# Voicecard-SMRMU-v02.net
KiCad netlist of a schematic drawn in EAGLE
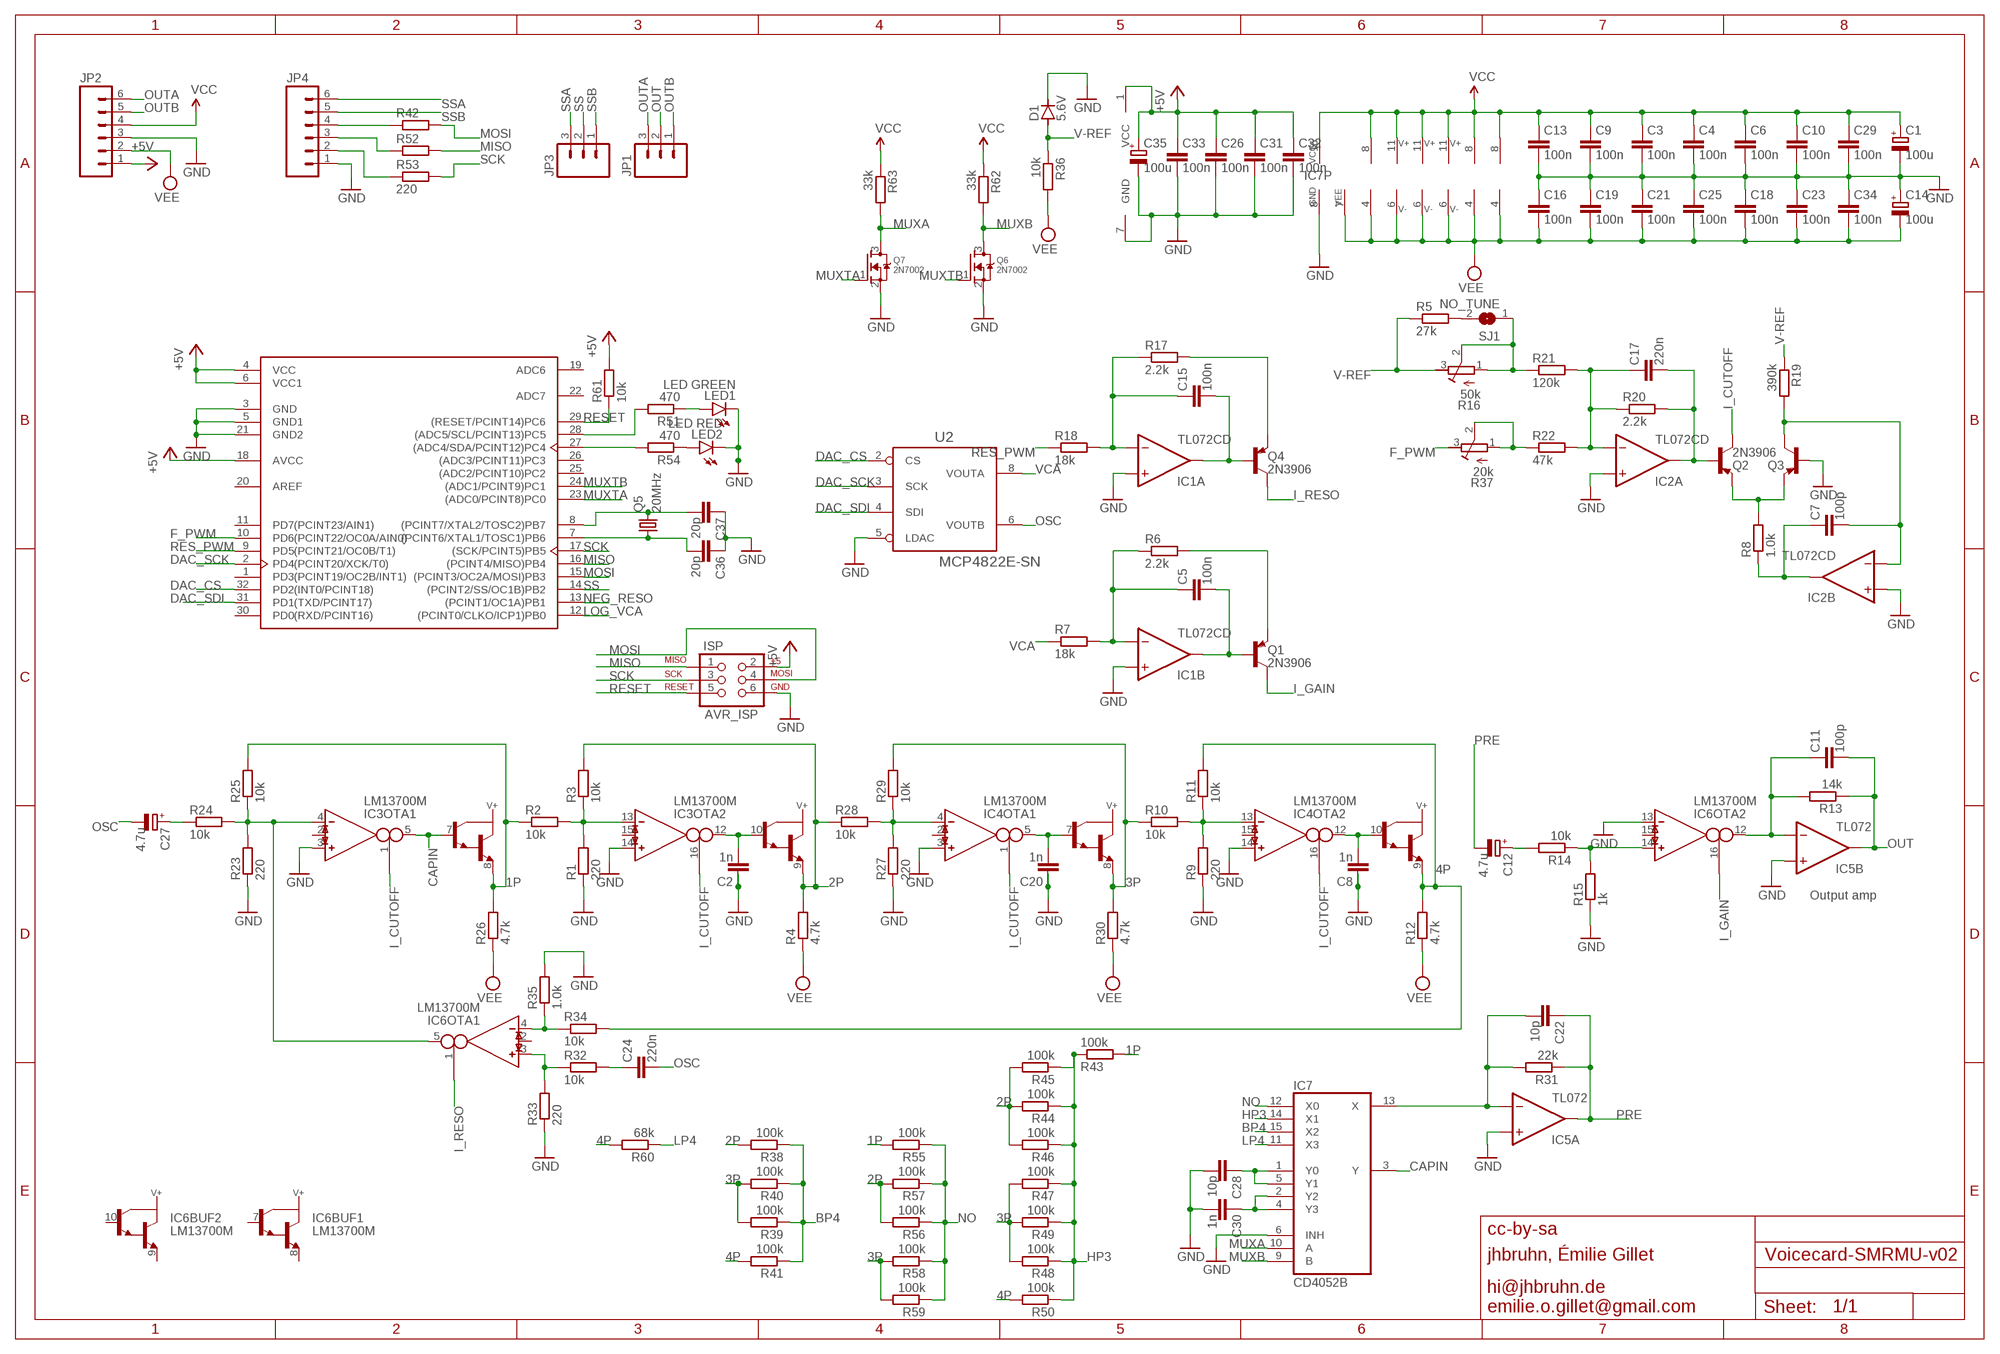
[diagram p0: schematic, sheet 1]

(export (version "E")
  (design (tool "Eeschema 10.0.6"))
  (components
    (comp (ref "C1")
      (value "100u")
      (footprint "eagle-import:UD-6,3X7,7_NICHICON")
      (libsource (lib "eagle-import") (part "CPOL-EUUD-6,3X7,7"))
    )
    (comp (ref "C2")
      (value "1n")
      (footprint "eagle-import:C0603")
      (libsource (lib "eagle-import") (part "C-EUC0603"))
    )
    (comp (ref "C3")
      (value "100n")
      (footprint "eagle-import:C0603")
      (libsource (lib "eagle-import") (part "C-EUC0603"))
    )
    (comp (ref "C4")
      (value "100n")
      (footprint "eagle-import:C0603")
      (libsource (lib "eagle-import") (part "C-EUC0603"))
    )
    (comp (ref "C5")
      (value "100n")
      (footprint "eagle-import:C0603")
      (libsource (lib "eagle-import") (part "C-EUC0603"))
    )
    (comp (ref "C6")
      (value "100n")
      (footprint "eagle-import:C0603")
      (libsource (lib "eagle-import") (part "C-EUC0603"))
    )
    (comp (ref "C7")
      (value "100p")
      (footprint "eagle-import:C0603")
      (libsource (lib "eagle-import") (part "C-EUC0603"))
    )
    (comp (ref "C8")
      (value "1n")
      (footprint "eagle-import:C0603")
      (libsource (lib "eagle-import") (part "C-EUC0603"))
    )
    (comp (ref "C9")
      (value "100n")
      (footprint "eagle-import:C0603")
      (libsource (lib "eagle-import") (part "C-EUC0603"))
    )
    (comp (ref "C10")
      (value "100n")
      (footprint "eagle-import:C0603")
      (libsource (lib "eagle-import") (part "C-EUC0603"))
    )
    (comp (ref "C11")
      (value "100p")
      (footprint "eagle-import:C0603")
      (libsource (lib "eagle-import") (part "C-EUC0603"))
    )
    (comp (ref "C12")
      (value "4.7u")
      (footprint "eagle-import:UD-5X5,8_NICHICON")
      (libsource (lib "eagle-import") (part "CPOL-EUUD-5X5,8"))
    )
    (comp (ref "C13")
      (value "100n")
      (footprint "eagle-import:C0603")
      (libsource (lib "eagle-import") (part "C-EUC0603"))
    )
    (comp (ref "C14")
      (value "100u")
      (footprint "eagle-import:UD-6,3X7,7_NICHICON")
      (libsource (lib "eagle-import") (part "CPOL-EUUD-6,3X7,7"))
    )
    (comp (ref "C15")
      (value "100n")
      (footprint "eagle-import:C0603")
      (libsource (lib "eagle-import") (part "C-EUC0603"))
    )
    (comp (ref "C16")
      (value "100n")
      (footprint "eagle-import:C0603")
      (libsource (lib "eagle-import") (part "C-EUC0603"))
    )
    (comp (ref "C17")
      (value "220n")
      (footprint "eagle-import:C0603")
      (libsource (lib "eagle-import") (part "C-EUC0603"))
    )
    (comp (ref "C18")
      (value "100n")
      (footprint "eagle-import:C0603")
      (libsource (lib "eagle-import") (part "C-EUC0603"))
    )
    (comp (ref "C19")
      (value "100n")
      (footprint "eagle-import:C0603")
      (libsource (lib "eagle-import") (part "C-EUC0603"))
    )
    (comp (ref "C20")
      (value "1n")
      (footprint "eagle-import:C0603")
      (libsource (lib "eagle-import") (part "C-EUC0603"))
    )
    (comp (ref "C21")
      (value "100n")
      (footprint "eagle-import:C0603")
      (libsource (lib "eagle-import") (part "C-EUC0603"))
    )
    (comp (ref "C22")
      (value "10p")
      (footprint "eagle-import:C0603")
      (libsource (lib "eagle-import") (part "C-EUC0603"))
    )
    (comp (ref "C23")
      (value "100n")
      (footprint "eagle-import:C0603")
      (libsource (lib "eagle-import") (part "C-EUC0603"))
    )
    (comp (ref "C24")
      (value "220n")
      (footprint "eagle-import:C0603")
      (libsource (lib "eagle-import") (part "C-EUC0603"))
    )
    (comp (ref "C25")
      (value "100n")
      (footprint "eagle-import:C0603")
      (libsource (lib "eagle-import") (part "C-EUC0603"))
    )
    (comp (ref "C26")
      (value "100n")
      (footprint "eagle-import:C0603")
      (libsource (lib "eagle-import") (part "C-EUC0603"))
    )
    (comp (ref "C27")
      (value "4.7u")
      (footprint "eagle-import:UD-5X5,8_NICHICON")
      (libsource (lib "eagle-import") (part "CPOL-EUUD-5X5,8"))
    )
    (comp (ref "C28")
      (value "10p")
      (footprint "eagle-import:C0603")
      (libsource (lib "eagle-import") (part "C-EUC0603"))
    )
    (comp (ref "C29")
      (value "100n")
      (footprint "eagle-import:C0603")
      (libsource (lib "eagle-import") (part "C-EUC0603"))
    )
    (comp (ref "C30")
      (value "1n")
      (footprint "eagle-import:C0603")
      (libsource (lib "eagle-import") (part "C-EUC0603"))
    )
    (comp (ref "C31")
      (value "100n")
      (footprint "eagle-import:C0603")
      (libsource (lib "eagle-import") (part "C-EUC0603"))
    )
    (comp (ref "C32")
      (value "100n")
      (footprint "eagle-import:C0603")
      (libsource (lib "eagle-import") (part "C-EUC0603"))
    )
    (comp (ref "C33")
      (value "100n")
      (footprint "eagle-import:C0603")
      (libsource (lib "eagle-import") (part "C-EUC0603"))
    )
    (comp (ref "C34")
      (value "100n")
      (footprint "eagle-import:C0603")
      (libsource (lib "eagle-import") (part "C-EUC0603"))
    )
    (comp (ref "C35")
      (value "100u")
      (footprint "eagle-import:UD-6,3X7,7_NICHICON")
      (libsource (lib "eagle-import") (part "CPOL-EUUD-6,3X7,7"))
    )
    (comp (ref "C36")
      (value "20p")
      (footprint "eagle-import:C0603")
      (libsource (lib "eagle-import") (part "C-EUC0603"))
    )
    (comp (ref "C37")
      (value "20p")
      (footprint "eagle-import:C0603")
      (libsource (lib "eagle-import") (part "C-EUC0603"))
    )
    (comp (ref "D1")
      (value "5.6V")
      (footprint "eagle-import:MELF-MLL34")
      (libsource (lib "eagle-import") (part "DIODE-LL-34"))
    )
    (comp (ref "IC1")
      (value "TL072CD")
      (footprint "eagle-import:SOIC8")
      (libsource (lib "eagle-import") (part "TL072DC"))
    )
    (comp (ref "IC2")
      (value "TL072CD")
      (footprint "eagle-import:SOIC8")
      (libsource (lib "eagle-import") (part "TL072DC"))
    )
    (comp (ref "IC3")
      (value "LM13700M")
      (footprint "eagle-import:SO16")
      (libsource (lib "eagle-import") (part "LM13700M"))
    )
    (comp (ref "IC4")
      (value "LM13700M")
      (footprint "eagle-import:SO16")
      (libsource (lib "eagle-import") (part "LM13700M"))
    )
    (comp (ref "IC5")
      (value "TL072")
      (footprint "eagle-import:SOIC8")
      (libsource (lib "eagle-import") (part "TL072DC"))
    )
    (comp (ref "IC6")
      (value "LM13700M")
      (footprint "eagle-import:SO16")
      (libsource (lib "eagle-import") (part "LM13700M"))
    )
    (comp (ref "IC7")
      (value "CD4052B")
      (footprint "eagle-import:SOIC16N")
      (libsource (lib "eagle-import") (part "CD4052B"))
    )
    (comp (ref "ISP")
      (value "AVR_ISP")
      (footprint "eagle-import:2X3")
      (libsource (lib "eagle-import") (part "AVR_SPI_PRG_6PTH"))
    )
    (comp (ref "JP1")
      (value "M03PTH")
      (footprint "eagle-import:1X03")
      (libsource (lib "eagle-import") (part "M03PTH"))
    )
    (comp (ref "JP2")
      (value "M06SIP")
      (footprint "eagle-import:1X06")
      (libsource (lib "eagle-import") (part "M06SIP"))
    )
    (comp (ref "JP3")
      (value "M03PTH")
      (footprint "eagle-import:1X03")
      (libsource (lib "eagle-import") (part "M03PTH"))
    )
    (comp (ref "JP4")
      (value "M06SIP")
      (footprint "eagle-import:1X06")
      (libsource (lib "eagle-import") (part "M06SIP"))
    )
    (comp (ref "LED1")
      (value "LED GREEN")
      (footprint "eagle-import:CHIP-LED0603")
      (libsource (lib "eagle-import") (part "LED"))
    )
    (comp (ref "LED2")
      (value "LED RED")
      (footprint "eagle-import:CHIP-LED0603")
      (libsource (lib "eagle-import") (part "LED"))
    )
    (comp (ref "Q1")
      (value "2N3906")
      (footprint "eagle-import:SOT23-BEC")
      (libsource (lib "eagle-import") (part "2N3906"))
    )
    (comp (ref "Q2")
      (value "2N3906")
      (footprint "eagle-import:SOT23-BEC")
      (libsource (lib "eagle-import") (part "2N3906"))
    )
    (comp (ref "Q3")
      (value "2N3906")
      (footprint "eagle-import:SOT23-BEC")
      (libsource (lib "eagle-import") (part "2N3906"))
    )
    (comp (ref "Q4")
      (value "2N3906")
      (footprint "eagle-import:SOT23-BEC")
      (libsource (lib "eagle-import") (part "2N3906"))
    )
    (comp (ref "Q5")
      (value "20MHz")
      (footprint "eagle-import:HC49UP")
      (libsource (lib "eagle-import") (part "CRYSTALHC49UP"))
    )
    (comp (ref "Q6")
      (value "2N7002")
      (footprint "eagle-import:SOT23")
      (libsource (lib "eagle-import") (part "MOSFET-NREFLOW"))
    )
    (comp (ref "Q7")
      (value "2N7002")
      (footprint "eagle-import:SOT23")
      (libsource (lib "eagle-import") (part "MOSFET-NREFLOW"))
    )
    (comp (ref "R1")
      (value "220")
      (footprint "eagle-import:R0603")
      (libsource (lib "eagle-import") (part "R-EU_R0603"))
    )
    (comp (ref "R2")
      (value "10k")
      (footprint "eagle-import:R0603")
      (libsource (lib "eagle-import") (part "R-EU_R0603"))
    )
    (comp (ref "R3")
      (value "10k")
      (footprint "eagle-import:R0603")
      (libsource (lib "eagle-import") (part "R-EU_R0603"))
    )
    (comp (ref "R4")
      (value "4.7k")
      (footprint "eagle-import:R0603")
      (libsource (lib "eagle-import") (part "R-EU_R0603"))
    )
    (comp (ref "R5")
      (value "27k")
      (footprint "eagle-import:R0603")
      (libsource (lib "eagle-import") (part "R-EU_R0603"))
    )
    (comp (ref "R6")
      (value "2.2k")
      (footprint "eagle-import:R0603")
      (libsource (lib "eagle-import") (part "R-EU_R0603"))
    )
    (comp (ref "R7")
      (value "18k")
      (footprint "eagle-import:R0603")
      (libsource (lib "eagle-import") (part "R-EU_R0603"))
    )
    (comp (ref "R8")
      (value "1.0k")
      (footprint "eagle-import:R0603")
      (libsource (lib "eagle-import") (part "R-EU_R0603"))
    )
    (comp (ref "R9")
      (value "220")
      (footprint "eagle-import:R0603")
      (libsource (lib "eagle-import") (part "R-EU_R0603"))
    )
    (comp (ref "R10")
      (value "10k")
      (footprint "eagle-import:R0603")
      (libsource (lib "eagle-import") (part "R-EU_R0603"))
    )
    (comp (ref "R11")
      (value "10k")
      (footprint "eagle-import:R0603")
      (libsource (lib "eagle-import") (part "R-EU_R0603"))
    )
    (comp (ref "R12")
      (value "4.7k")
      (footprint "eagle-import:R0603")
      (libsource (lib "eagle-import") (part "R-EU_R0603"))
    )
    (comp (ref "R13")
      (value "14k")
      (footprint "eagle-import:R0603")
      (libsource (lib "eagle-import") (part "R-EU_R0603"))
    )
    (comp (ref "R14")
      (value "10k")
      (footprint "eagle-import:R0603")
      (libsource (lib "eagle-import") (part "R-EU_R0603"))
    )
    (comp (ref "R15")
      (value "1k")
      (footprint "eagle-import:R0603")
      (libsource (lib "eagle-import") (part "R-EU_R0603"))
    )
    (comp (ref "R16")
      (value "50k")
      (footprint "eagle-import:RTRIM3296P")
      (libsource (lib "eagle-import") (part "R-TRIMM3296P"))
    )
    (comp (ref "R17")
      (value "2.2k")
      (footprint "eagle-import:R0603")
      (libsource (lib "eagle-import") (part "R-EU_R0603"))
    )
    (comp (ref "R18")
      (value "18k")
      (footprint "eagle-import:R0603")
      (libsource (lib "eagle-import") (part "R-EU_R0603"))
    )
    (comp (ref "R19")
      (value "390k")
      (footprint "eagle-import:R0603")
      (libsource (lib "eagle-import") (part "R-EU_R0603"))
    )
    (comp (ref "R20")
      (value "2.2k")
      (footprint "eagle-import:R0603")
      (libsource (lib "eagle-import") (part "R-EU_R0603"))
    )
    (comp (ref "R21")
      (value "120k")
      (footprint "eagle-import:R0603")
      (libsource (lib "eagle-import") (part "R-EU_R0603"))
    )
    (comp (ref "R22")
      (value "47k")
      (footprint "eagle-import:R0603")
      (libsource (lib "eagle-import") (part "R-EU_R0603"))
    )
    (comp (ref "R23")
      (value "220")
      (footprint "eagle-import:R0603")
      (libsource (lib "eagle-import") (part "R-EU_R0603"))
    )
    (comp (ref "R24")
      (value "10k")
      (footprint "eagle-import:R0603")
      (libsource (lib "eagle-import") (part "R-EU_R0603"))
    )
    (comp (ref "R25")
      (value "10k")
      (footprint "eagle-import:R0603")
      (libsource (lib "eagle-import") (part "R-EU_R0603"))
    )
    (comp (ref "R26")
      (value "4.7k")
      (footprint "eagle-import:R0603")
      (libsource (lib "eagle-import") (part "R-EU_R0603"))
    )
    (comp (ref "R27")
      (value "220")
      (footprint "eagle-import:R0603")
      (libsource (lib "eagle-import") (part "R-EU_R0603"))
    )
    (comp (ref "R28")
      (value "10k")
      (footprint "eagle-import:R0603")
      (libsource (lib "eagle-import") (part "R-EU_R0603"))
    )
    (comp (ref "R29")
      (value "10k")
      (footprint "eagle-import:R0603")
      (libsource (lib "eagle-import") (part "R-EU_R0603"))
    )
    (comp (ref "R30")
      (value "4.7k")
      (footprint "eagle-import:R0603")
      (libsource (lib "eagle-import") (part "R-EU_R0603"))
    )
    (comp (ref "R31")
      (value "22k")
      (footprint "eagle-import:R0603")
      (libsource (lib "eagle-import") (part "R-EU_R0603"))
    )
    (comp (ref "R32")
      (value "10k")
      (footprint "eagle-import:R0603")
      (libsource (lib "eagle-import") (part "R-EU_R0603"))
    )
    (comp (ref "R33")
      (value "220")
      (footprint "eagle-import:R0603")
      (libsource (lib "eagle-import") (part "R-EU_R0603"))
    )
    (comp (ref "R34")
      (value "10k")
      (footprint "eagle-import:R0603")
      (libsource (lib "eagle-import") (part "R-EU_R0603"))
    )
    (comp (ref "R35")
      (value "1.0k")
      (footprint "eagle-import:R0603")
      (libsource (lib "eagle-import") (part "R-EU_R0603"))
    )
    (comp (ref "R36")
      (value "10k")
      (footprint "eagle-import:R0603")
      (libsource (lib "eagle-import") (part "R-EU_R0603"))
    )
    (comp (ref "R37")
      (value "20k")
      (footprint "eagle-import:RTRIM3296P")
      (libsource (lib "eagle-import") (part "R-TRIMM3296P"))
    )
    (comp (ref "R38")
      (value "100k")
      (footprint "eagle-import:R0603")
      (libsource (lib "eagle-import") (part "R-EU_R0603"))
    )
    (comp (ref "R39")
      (value "100k")
      (footprint "eagle-import:R0603")
      (libsource (lib "eagle-import") (part "R-EU_R0603"))
    )
    (comp (ref "R40")
      (value "100k")
      (footprint "eagle-import:R0603")
      (libsource (lib "eagle-import") (part "R-EU_R0603"))
    )
    (comp (ref "R41")
      (value "100k")
      (footprint "eagle-import:R0603")
      (libsource (lib "eagle-import") (part "R-EU_R0603"))
    )
    (comp (ref "R42")
      (value "220")
      (footprint "eagle-import:R0603")
      (libsource (lib "eagle-import") (part "R-EU_R0603"))
    )
    (comp (ref "R43")
      (value "100k")
      (footprint "eagle-import:R0603")
      (libsource (lib "eagle-import") (part "R-EU_R0603"))
    )
    (comp (ref "R44")
      (value "100k")
      (footprint "eagle-import:R0603")
      (libsource (lib "eagle-import") (part "R-EU_R0603"))
    )
    (comp (ref "R45")
      (value "100k")
      (footprint "eagle-import:R0603")
      (libsource (lib "eagle-import") (part "R-EU_R0603"))
    )
    (comp (ref "R46")
      (value "100k")
      (footprint "eagle-import:R0603")
      (libsource (lib "eagle-import") (part "R-EU_R0603"))
    )
    (comp (ref "R47")
      (value "100k")
      (footprint "eagle-import:R0603")
      (libsource (lib "eagle-import") (part "R-EU_R0603"))
    )
    (comp (ref "R48")
      (value "100k")
      (footprint "eagle-import:R0603")
      (libsource (lib "eagle-import") (part "R-EU_R0603"))
    )
    (comp (ref "R49")
      (value "100k")
      (footprint "eagle-import:R0603")
      (libsource (lib "eagle-import") (part "R-EU_R0603"))
    )
    (comp (ref "R50")
      (value "100k")
      (footprint "eagle-import:R0603")
      (libsource (lib "eagle-import") (part "R-EU_R0603"))
    )
    (comp (ref "R51")
      (value "470")
      (footprint "eagle-import:R0603")
      (libsource (lib "eagle-import") (part "R-EU_R0603"))
    )
    (comp (ref "R52")
      (value "220")
      (footprint "eagle-import:R0603")
      (libsource (lib "eagle-import") (part "R-EU_R0603"))
    )
    (comp (ref "R53")
      (value "220")
      (footprint "eagle-import:R0603")
      (libsource (lib "eagle-import") (part "R-EU_R0603"))
    )
    (comp (ref "R54")
      (value "470")
      (footprint "eagle-import:R0603")
      (libsource (lib "eagle-import") (part "R-EU_R0603"))
    )
    (comp (ref "R55")
      (value "100k")
      (footprint "eagle-import:R0603")
      (libsource (lib "eagle-import") (part "R-EU_R0603"))
    )
    (comp (ref "R56")
      (value "100k")
      (footprint "eagle-import:R0603")
      (libsource (lib "eagle-import") (part "R-EU_R0603"))
    )
    (comp (ref "R57")
      (value "100k")
      (footprint "eagle-import:R0603")
      (libsource (lib "eagle-import") (part "R-EU_R0603"))
    )
    (comp (ref "R58")
      (value "100k")
      (footprint "eagle-import:R0603")
      (libsource (lib "eagle-import") (part "R-EU_R0603"))
    )
    (comp (ref "R59")
      (value "100k")
      (footprint "eagle-import:R0603")
      (libsource (lib "eagle-import") (part "R-EU_R0603"))
    )
    (comp (ref "R60")
      (value "68k")
      (footprint "eagle-import:R0603")
      (libsource (lib "eagle-import") (part "R-EU_R0603"))
    )
    (comp (ref "R61")
      (value "10k")
      (footprint "eagle-import:R0603")
      (libsource (lib "eagle-import") (part "R-EU_R0603"))
    )
    (comp (ref "R62")
      (value "33k")
      (footprint "eagle-import:R0603")
      (libsource (lib "eagle-import") (part "R-EU_R0603"))
    )
    (comp (ref "R63")
      (value "33k")
      (footprint "eagle-import:R0603")
      (libsource (lib "eagle-import") (part "R-EU_R0603"))
    )
    (comp (ref "SJ1")
      (value "NO_TUNE")
      (footprint "eagle-import:SJ")
      (libsource (lib "eagle-import") (part "SJ"))
    )
    (comp (ref "U1")
      (value "ATMEGA328P-AU")
      (footprint "eagle-import:TQFP-32")
      (fields
        (field (name "DIGIKEY_PART_NUMBER") "ATMEGA328P-AU-ND")
        (field (name "MANUFACTURER") "Microchip Technology")
        (field (name "CREATED_BY") "PCBLayout.com")
      )
      (libsource (lib "eagle-import") (part "ATMEGA328P-AU"))
    )
    (comp (ref "U2")
      (value "MCP4822E-SN")
      (footprint "eagle-import:SOIC8")
      (libsource (lib "eagle-import") (part "MCP482E-SN2"))
    )
  )
  (nets
    (net (code "1") (name "+5V") (class "Default")
      (node (ref "C26") (pin "1") (pinfunction "1_1") (pintype "passive"))
      (node (ref "C31") (pin "1") (pinfunction "1_1") (pintype "passive"))
      (node (ref "C32") (pin "1") (pinfunction "1_1") (pintype "passive"))
      (node (ref "C33") (pin "1") (pinfunction "1_1") (pintype "passive"))
      (node (ref "C35") (pin "+") (pinfunction "+_+") (pintype "passive"))
      (node (ref "ISP") (pin "2") (pinfunction "2_2") (pintype "passive"))
      (node (ref "JP2") (pin "1") (pinfunction "1_1") (pintype "passive"))
      (node (ref "R61") (pin "2") (pinfunction "2_2") (pintype "passive"))
      (node (ref "U1") (pin "18") (pinfunction "AVCC_18") (pintype "power_in"))
      (node (ref "U1") (pin "4") (pinfunction "VCC_4") (pintype "power_in"))
      (node (ref "U1") (pin "6") (pinfunction "VCC1_6") (pintype "power_in"))
      (node (ref "U2") (pin "1") (pinfunction "VCC_1") (pintype "power_in"))
    )
    (net (code "2") (name "/1P") (class "Default")
      (node (ref "IC3") (pin "8") (pinfunction "E_8") (pintype "passive"))
      (node (ref "R2") (pin "1") (pinfunction "1_1") (pintype "passive"))
      (node (ref "R25") (pin "2") (pinfunction "2_2") (pintype "passive"))
      (node (ref "R26") (pin "2") (pinfunction "2_2") (pintype "passive"))
      (node (ref "R43") (pin "2") (pinfunction "2_2") (pintype "passive"))
      (node (ref "R55") (pin "2") (pinfunction "2_2") (pintype "passive"))
    )
    (net (code "3") (name "/2P") (class "Default")
      (node (ref "IC3") (pin "9") (pinfunction "E_9") (pintype "passive"))
      (node (ref "R28") (pin "1") (pinfunction "1_1") (pintype "passive"))
      (node (ref "R3") (pin "2") (pinfunction "2_2") (pintype "passive"))
      (node (ref "R38") (pin "2") (pinfunction "2_2") (pintype "passive"))
      (node (ref "R4") (pin "2") (pinfunction "2_2") (pintype "passive"))
      (node (ref "R44") (pin "2") (pinfunction "2_2") (pintype "passive"))
      (node (ref "R45") (pin "2") (pinfunction "2_2") (pintype "passive"))
      (node (ref "R46") (pin "2") (pinfunction "2_2") (pintype "passive"))
      (node (ref "R56") (pin "2") (pinfunction "2_2") (pintype "passive"))
      (node (ref "R57") (pin "2") (pinfunction "2_2") (pintype "passive"))
    )
    (net (code "4") (name "/3P") (class "Default")
      (node (ref "IC4") (pin "8") (pinfunction "E_8") (pintype "passive"))
      (node (ref "R10") (pin "1") (pinfunction "1_1") (pintype "passive"))
      (node (ref "R29") (pin "2") (pinfunction "2_2") (pintype "passive"))
      (node (ref "R30") (pin "2") (pinfunction "2_2") (pintype "passive"))
      (node (ref "R39") (pin "2") (pinfunction "2_2") (pintype "passive"))
      (node (ref "R40") (pin "2") (pinfunction "2_2") (pintype "passive"))
      (node (ref "R47") (pin "2") (pinfunction "2_2") (pintype "passive"))
      (node (ref "R48") (pin "2") (pinfunction "2_2") (pintype "passive"))
      (node (ref "R49") (pin "2") (pinfunction "2_2") (pintype "passive"))
      (node (ref "R58") (pin "2") (pinfunction "2_2") (pintype "passive"))
      (node (ref "R59") (pin "2") (pinfunction "2_2") (pintype "passive"))
    )
    (net (code "5") (name "/4P") (class "Default")
      (node (ref "IC4") (pin "9") (pinfunction "E_9") (pintype "passive"))
      (node (ref "R11") (pin "2") (pinfunction "2_2") (pintype "passive"))
      (node (ref "R12") (pin "2") (pinfunction "2_2") (pintype "passive"))
      (node (ref "R34") (pin "2") (pinfunction "2_2") (pintype "passive"))
      (node (ref "R41") (pin "2") (pinfunction "2_2") (pintype "passive"))
      (node (ref "R50") (pin "2") (pinfunction "2_2") (pintype "passive"))
      (node (ref "R60") (pin "2") (pinfunction "2_2") (pintype "passive"))
    )
    (net (code "6") (name "/AREF") (class "Default")
      (node (ref "U1") (pin "20") (pinfunction "AREF_20") (pintype "power_in"))
    )
    (net (code "7") (name "/BP4") (class "Default")
      (node (ref "IC7") (pin "15") (pinfunction "X2_15") (pintype "bidirectional"))
      (node (ref "R38") (pin "1") (pinfunction "1_1") (pintype "passive"))
      (node (ref "R39") (pin "1") (pinfunction "1_1") (pintype "passive"))
      (node (ref "R40") (pin "1") (pinfunction "1_1") (pintype "passive"))
      (node (ref "R41") (pin "1") (pinfunction "1_1") (pintype "passive"))
    )
    (net (code "8") (name "/CAPIN") (class "Default")
      (node (ref "IC3") (pin "5") (pinfunction "OUT_5") (pintype "output"))
      (node (ref "IC3") (pin "7") (pinfunction "B_7") (pintype "passive"))
      (node (ref "IC7") (pin "3") (pinfunction "Y_3") (pintype "bidirectional"))
    )
    (net (code "9") (name "/DAC_CS") (class "Default")
      (node (ref "U1") (pin "32") (pinfunction "PD2(INT0/PCINT18)_32") (pintype "bidirectional"))
      (node (ref "U2") (pin "2") (pinfunction "CS_2") (pintype "input"))
    )
    (net (code "10") (name "/DAC_SCK") (class "Default")
      (node (ref "U1") (pin "2") (pinfunction "PD4(PCINT20/XCK/T0)_2") (pintype "bidirectional"))
      (node (ref "U2") (pin "3") (pinfunction "SCK_3") (pintype "input"))
    )
    (net (code "11") (name "/DAC_SDI") (class "Default")
      (node (ref "U1") (pin "31") (pinfunction "PD1(TXD/PCINT17)_31") (pintype "bidirectional"))
      (node (ref "U2") (pin "4") (pinfunction "SDI_4") (pintype "input"))
    )
    (net (code "12") (name "/F_PWM") (class "Default")
      (node (ref "R37") (pin "3") (pinfunction "E_3") (pintype "passive"))
      (node (ref "U1") (pin "10") (pinfunction "PD6(PCINT22/OC0A/AIN0)_10") (pintype "bidirectional"))
    )
    (net (code "13") (name "/HP3") (class "Default")
      (node (ref "IC7") (pin "14") (pinfunction "X1_14") (pintype "bidirectional"))
      (node (ref "R43") (pin "1") (pinfunction "1_1") (pintype "passive"))
      (node (ref "R44") (pin "1") (pinfunction "1_1") (pintype "passive"))
      (node (ref "R45") (pin "1") (pinfunction "1_1") (pintype "passive"))
      (node (ref "R46") (pin "1") (pinfunction "1_1") (pintype "passive"))
      (node (ref "R47") (pin "1") (pinfunction "1_1") (pintype "passive"))
      (node (ref "R48") (pin "1") (pinfunction "1_1") (pintype "passive"))
      (node (ref "R49") (pin "1") (pinfunction "1_1") (pintype "passive"))
      (node (ref "R50") (pin "1") (pinfunction "1_1") (pintype "passive"))
    )
    (net (code "14") (name "/I_CUTOFF") (class "Default")
      (node (ref "IC3") (pin "1") (pinfunction "I_BIAS_1") (pintype "input"))
      (node (ref "IC3") (pin "16") (pinfunction "I_BIAS_16") (pintype "input"))
      (node (ref "IC4") (pin "1") (pinfunction "I_BIAS_1") (pintype "input"))
      (node (ref "IC4") (pin "16") (pinfunction "I_BIAS_16") (pintype "input"))
      (node (ref "Q2") (pin "C") (pinfunction "C_C") (pintype "passive"))
    )
    (net (code "15") (name "/I_GAIN") (class "Default")
      (node (ref "IC6") (pin "16") (pinfunction "I_BIAS_16") (pintype "input"))
      (node (ref "Q1") (pin "C") (pinfunction "C_C") (pintype "passive"))
    )
    (net (code "16") (name "/I_RESO") (class "Default")
      (node (ref "IC6") (pin "1") (pinfunction "I_BIAS_1") (pintype "input"))
      (node (ref "Q4") (pin "C") (pinfunction "C_C") (pintype "passive"))
    )
    (net (code "17") (name "/LOG_VCA") (class "Default")
      (node (ref "U1") (pin "12") (pinfunction "(PCINT0/CLKO/ICP1)PB0_12") (pintype "bidirectional"))
    )
    (net (code "18") (name "/LP4") (class "Default")
      (node (ref "IC7") (pin "11") (pinfunction "X3_11") (pintype "bidirectional"))
      (node (ref "R60") (pin "1") (pinfunction "1_1") (pintype "passive"))
    )
    (net (code "19") (name "/MISO") (class "Default")
      (node (ref "ISP") (pin "1") (pinfunction "1_1") (pintype "passive"))
      (node (ref "R52") (pin "2") (pinfunction "2_2") (pintype "passive"))
      (node (ref "U1") (pin "16") (pinfunction "(PCINT4/MISO)PB4_16") (pintype "bidirectional"))
    )
    (net (code "20") (name "/MOSI") (class "Default")
      (node (ref "ISP") (pin "4") (pinfunction "4_4") (pintype "passive"))
      (node (ref "R42") (pin "2") (pinfunction "2_2") (pintype "passive"))
      (node (ref "U1") (pin "15") (pinfunction "(PCINT3/OC2A/MOSI)PB3_15") (pintype "bidirectional"))
    )
    (net (code "21") (name "/MUXA") (class "Default")
      (node (ref "IC7") (pin "10") (pinfunction "A_10") (pintype "input"))
      (node (ref "Q7") (pin "3") (pinfunction "D_3") (pintype "bidirectional"))
      (node (ref "R63") (pin "2") (pinfunction "2_2") (pintype "passive"))
    )
    (net (code "22") (name "/MUXB") (class "Default")
      (node (ref "IC7") (pin "9") (pinfunction "B_9") (pintype "input"))
      (node (ref "Q6") (pin "3") (pinfunction "D_3") (pintype "bidirectional"))
      (node (ref "R62") (pin "2") (pinfunction "2_2") (pintype "passive"))
    )
    (net (code "23") (name "/MUXTA") (class "Default")
      (node (ref "Q7") (pin "1") (pinfunction "G_1") (pintype "bidirectional"))
      (node (ref "U1") (pin "23") (pinfunction "(ADC0/PCINT8)PC0_23") (pintype "bidirectional"))
    )
    (net (code "24") (name "/MUXTB") (class "Default")
      (node (ref "Q6") (pin "1") (pinfunction "G_1") (pintype "bidirectional"))
      (node (ref "U1") (pin "24") (pinfunction "(ADC1/PCINT9)PC1_24") (pintype "bidirectional"))
    )
    (net (code "25") (name "/NEG_RESO") (class "Default")
      (node (ref "U1") (pin "13") (pinfunction "(PCINT1/OC1A)PB1_13") (pintype "bidirectional"))
    )
    (net (code "26") (name "/NO") (class "Default")
      (node (ref "IC7") (pin "12") (pinfunction "X0_12") (pintype "bidirectional"))
      (node (ref "R55") (pin "1") (pinfunction "1_1") (pintype "passive"))
      (node (ref "R56") (pin "1") (pinfunction "1_1") (pintype "passive"))
      (node (ref "R57") (pin "1") (pinfunction "1_1") (pintype "passive"))
      (node (ref "R58") (pin "1") (pinfunction "1_1") (pintype "passive"))
      (node (ref "R59") (pin "1") (pinfunction "1_1") (pintype "passive"))
    )
    (net (code "27") (name "/OSC") (class "Default")
      (node (ref "C24") (pin "2") (pinfunction "2_2") (pintype "passive"))
      (node (ref "C27") (pin "-") (pinfunction "-_-") (pintype "passive"))
      (node (ref "U2") (pin "6") (pinfunction "VOUTB_6") (pintype "output"))
    )
    (net (code "28") (name "/OUT") (class "Default")
      (node (ref "C11") (pin "2") (pinfunction "2_2") (pintype "passive"))
      (node (ref "IC5") (pin "7") (pinfunction "OUT_7") (pintype "output"))
      (node (ref "JP1") (pin "2") (pinfunction "2_2") (pintype "passive"))
      (node (ref "R13") (pin "1") (pinfunction "1_1") (pintype "passive"))
    )
    (net (code "29") (name "/OUTA") (class "Default")
      (node (ref "JP1") (pin "3") (pinfunction "3_3") (pintype "passive"))
      (node (ref "JP2") (pin "6") (pinfunction "6_6") (pintype "passive"))
    )
    (net (code "30") (name "/OUTB") (class "Default")
      (node (ref "JP1") (pin "1") (pinfunction "1_1") (pintype "passive"))
      (node (ref "JP2") (pin "5") (pinfunction "5_5") (pintype "passive"))
    )
    (net (code "31") (name "/PRE") (class "Default")
      (node (ref "C12") (pin "-") (pinfunction "-_-") (pintype "passive"))
      (node (ref "C22") (pin "1") (pinfunction "1_1") (pintype "passive"))
      (node (ref "IC5") (pin "1") (pinfunction "OUT_1") (pintype "output"))
      (node (ref "R31") (pin "1") (pinfunction "1_1") (pintype "passive"))
    )
    (net (code "32") (name "/RESET") (class "Default")
      (node (ref "ISP") (pin "5") (pinfunction "5_5") (pintype "passive"))
      (node (ref "R61") (pin "1") (pinfunction "1_1") (pintype "passive"))
      (node (ref "U1") (pin "29") (pinfunction "(RESET/PCINT14)PC6_29") (pintype "bidirectional"))
    )
    (net (code "33") (name "/RES_PWM") (class "Default")
      (node (ref "R18") (pin "1") (pinfunction "1_1") (pintype "passive"))
      (node (ref "U1") (pin "9") (pinfunction "PD5(PCINT21/OC0B/T1)_9") (pintype "bidirectional"))
    )
    (net (code "34") (name "/SCK") (class "Default")
      (node (ref "ISP") (pin "3") (pinfunction "3_3") (pintype "passive"))
      (node (ref "R53") (pin "2") (pinfunction "2_2") (pintype "passive"))
      (node (ref "U1") (pin "17") (pinfunction "(SCK/PCINT5)PB5_17") (pintype "bidirectional"))
    )
    (net (code "35") (name "/SS") (class "Default")
      (node (ref "JP3") (pin "2") (pinfunction "2_2") (pintype "passive"))
      (node (ref "U1") (pin "14") (pinfunction "(PCINT2/SS/OC1B)PB2_14") (pintype "bidirectional"))
    )
    (net (code "36") (name "/SSA") (class "Default")
      (node (ref "JP3") (pin "3") (pinfunction "3_3") (pintype "passive"))
      (node (ref "JP4") (pin "6") (pinfunction "6_6") (pintype "passive"))
    )
    (net (code "37") (name "/SSB") (class "Default")
      (node (ref "JP3") (pin "1") (pinfunction "1_1") (pintype "passive"))
      (node (ref "JP4") (pin "5") (pinfunction "5_5") (pintype "passive"))
    )
    (net (code "38") (name "/V-REF") (class "Default")
      (node (ref "D1") (pin "2") (pinfunction "A_2") (pintype "passive"))
      (node (ref "R16") (pin "3") (pinfunction "E_3") (pintype "passive"))
      (node (ref "R19") (pin "1") (pinfunction "1_1") (pintype "passive"))
      (node (ref "R36") (pin "1") (pinfunction "1_1") (pintype "passive"))
      (node (ref "R5") (pin "1") (pinfunction "1_1") (pintype "passive"))
    )
    (net (code "39") (name "/VCA") (class "Default")
      (node (ref "R7") (pin "1") (pinfunction "1_1") (pintype "passive"))
      (node (ref "U2") (pin "8") (pinfunction "VOUTA_8") (pintype "output"))
    )
    (net (code "40") (name "GND") (class "Default")
      (node (ref "C1") (pin "-") (pinfunction "-_-") (pintype "passive"))
      (node (ref "C10") (pin "2") (pinfunction "2_2") (pintype "passive"))
      (node (ref "C13") (pin "2") (pinfunction "2_2") (pintype "passive"))
      (node (ref "C14") (pin "+") (pinfunction "+_+") (pintype "passive"))
      (node (ref "C16") (pin "1") (pinfunction "1_1") (pintype "passive"))
      (node (ref "C18") (pin "1") (pinfunction "1_1") (pintype "passive"))
      (node (ref "C19") (pin "1") (pinfunction "1_1") (pintype "passive"))
      (node (ref "C2") (pin "1") (pinfunction "1_1") (pintype "passive"))
      (node (ref "C20") (pin "1") (pinfunction "1_1") (pintype "passive"))
      (node (ref "C21") (pin "1") (pinfunction "1_1") (pintype "passive"))
      (node (ref "C23") (pin "1") (pinfunction "1_1") (pintype "passive"))
      (node (ref "C25") (pin "1") (pinfunction "1_1") (pintype "passive"))
      (node (ref "C26") (pin "2") (pinfunction "2_2") (pintype "passive"))
      (node (ref "C28") (pin "2") (pinfunction "2_2") (pintype "passive"))
      (node (ref "C29") (pin "2") (pinfunction "2_2") (pintype "passive"))
      (node (ref "C3") (pin "2") (pinfunction "2_2") (pintype "passive"))
      (node (ref "C30") (pin "2") (pinfunction "2_2") (pintype "passive"))
      (node (ref "C31") (pin "2") (pinfunction "2_2") (pintype "passive"))
      (node (ref "C32") (pin "2") (pinfunction "2_2") (pintype "passive"))
      (node (ref "C33") (pin "2") (pinfunction "2_2") (pintype "passive"))
      (node (ref "C34") (pin "1") (pinfunction "1_1") (pintype "passive"))
      (node (ref "C35") (pin "-") (pinfunction "-_-") (pintype "passive"))
      (node (ref "C36") (pin "1") (pinfunction "1_1") (pintype "passive"))
      (node (ref "C37") (pin "1") (pinfunction "1_1") (pintype "passive"))
      (node (ref "C4") (pin "2") (pinfunction "2_2") (pintype "passive"))
      (node (ref "C6") (pin "2") (pinfunction "2_2") (pintype "passive"))
      (node (ref "C8") (pin "1") (pinfunction "1_1") (pintype "passive"))
      (node (ref "C9") (pin "2") (pinfunction "2_2") (pintype "passive"))
      (node (ref "D1") (pin "1") (pinfunction "C_1") (pintype "passive"))
      (node (ref "IC1") (pin "3") (pinfunction "+IN_3") (pintype "input"))
      (node (ref "IC1") (pin "5") (pinfunction "+IN_5") (pintype "input"))
      (node (ref "IC2") (pin "3") (pinfunction "+IN_3") (pintype "input"))
      (node (ref "IC2") (pin "5") (pinfunction "+IN_5") (pintype "input"))
      (node (ref "IC3") (pin "14") (pinfunction "IN_P_14") (pintype "input"))
      (node (ref "IC3") (pin "3") (pinfunction "IN_P_3") (pintype "input"))
      (node (ref "IC4") (pin "14") (pinfunction "IN_P_14") (pintype "input"))
      (node (ref "IC4") (pin "3") (pinfunction "IN_P_3") (pintype "input"))
      (node (ref "IC5") (pin "3") (pinfunction "+IN_3") (pintype "input"))
      (node (ref "IC5") (pin "5") (pinfunction "+IN_5") (pintype "input"))
      (node (ref "IC6") (pin "13") (pinfunction "IN_N_13") (pintype "input"))
      (node (ref "IC7") (pin "6") (pinfunction "INH_6") (pintype "input"))
      (node (ref "IC7") (pin "8") (pinfunction "GND_8") (pintype "power_in"))
      (node (ref "ISP") (pin "6") (pinfunction "6_6") (pintype "passive"))
      (node (ref "JP2") (pin "3") (pinfunction "3_3") (pintype "passive"))
      (node (ref "JP4") (pin "1") (pinfunction "1_1") (pintype "passive"))
      (node (ref "LED1") (pin "C") (pinfunction "C_C") (pintype "passive"))
      (node (ref "LED2") (pin "C") (pinfunction "C_C") (pintype "passive"))
      (node (ref "Q3") (pin "B") (pinfunction "B_B") (pintype "passive"))
      (node (ref "Q6") (pin "2") (pinfunction "S_2") (pintype "bidirectional"))
      (node (ref "Q7") (pin "2") (pinfunction "S_2") (pintype "bidirectional"))
      (node (ref "R1") (pin "1") (pinfunction "1_1") (pintype "passive"))
      (node (ref "R15") (pin "1") (pinfunction "1_1") (pintype "passive"))
      (node (ref "R23") (pin "1") (pinfunction "1_1") (pintype "passive"))
      (node (ref "R27") (pin "1") (pinfunction "1_1") (pintype "passive"))
      (node (ref "R33") (pin "1") (pinfunction "1_1") (pintype "passive"))
      (node (ref "R35") (pin "2") (pinfunction "2_2") (pintype "passive"))
      (node (ref "R9") (pin "1") (pinfunction "1_1") (pintype "passive"))
      (node (ref "U1") (pin "21") (pinfunction "GND2_21") (pintype "power_in"))
      (node (ref "U1") (pin "3") (pinfunction "GND_3") (pintype "power_in"))
      (node (ref "U1") (pin "5") (pinfunction "GND1_5") (pintype "power_in"))
      (node (ref "U2") (pin "5") (pinfunction "LDAC_5") (pintype "input"))
      (node (ref "U2") (pin "7") (pinfunction "GND_7") (pintype "power_in"))
    )
    (net (code "41") (name "Net-(C12-Pad+)") (class "Default")
      (node (ref "C12") (pin "+") (pinfunction "+_+") (pintype "passive"))
      (node (ref "R14") (pin "2") (pinfunction "2_2") (pintype "passive"))
    )
    (net (code "42") (name "Net-(C24-Pad1)") (class "Default")
      (node (ref "C24") (pin "1") (pinfunction "1_1") (pintype "passive"))
      (node (ref "R32") (pin "2") (pinfunction "2_2") (pintype "passive"))
    )
    (net (code "43") (name "Net-(C27-Pad+)") (class "Default")
      (node (ref "C27") (pin "+") (pinfunction "+_+") (pintype "passive"))
      (node (ref "R24") (pin "1") (pinfunction "1_1") (pintype "passive"))
    )
    (net (code "44") (name "Net-(IC1A--IN)") (class "Default")
      (node (ref "C15") (pin "1") (pinfunction "1_1") (pintype "passive"))
      (node (ref "IC1") (pin "2") (pinfunction "-IN_2") (pintype "input"))
      (node (ref "R17") (pin "1") (pinfunction "1_1") (pintype "passive"))
      (node (ref "R18") (pin "2") (pinfunction "2_2") (pintype "passive"))
    )
    (net (code "45") (name "Net-(IC1A-OUT)") (class "Default")
      (node (ref "C15") (pin "2") (pinfunction "2_2") (pintype "passive"))
      (node (ref "IC1") (pin "1") (pinfunction "OUT_1") (pintype "output"))
      (node (ref "Q4") (pin "B") (pinfunction "B_B") (pintype "passive"))
    )
    (net (code "46") (name "Net-(IC1B--IN)") (class "Default")
      (node (ref "C5") (pin "1") (pinfunction "1_1") (pintype "passive"))
      (node (ref "IC1") (pin "6") (pinfunction "-IN_6") (pintype "input"))
      (node (ref "R6") (pin "1") (pinfunction "1_1") (pintype "passive"))
      (node (ref "R7") (pin "2") (pinfunction "2_2") (pintype "passive"))
    )
    (net (code "47") (name "Net-(IC1B-OUT)") (class "Default")
      (node (ref "C5") (pin "2") (pinfunction "2_2") (pintype "passive"))
      (node (ref "IC1") (pin "7") (pinfunction "OUT_7") (pintype "output"))
      (node (ref "Q1") (pin "B") (pinfunction "B_B") (pintype "passive"))
    )
    (net (code "48") (name "Net-(IC2A--IN)") (class "Default")
      (node (ref "C17") (pin "1") (pinfunction "1_1") (pintype "passive"))
      (node (ref "IC2") (pin "2") (pinfunction "-IN_2") (pintype "input"))
      (node (ref "R20") (pin "1") (pinfunction "1_1") (pintype "passive"))
      (node (ref "R21") (pin "2") (pinfunction "2_2") (pintype "passive"))
      (node (ref "R22") (pin "2") (pinfunction "2_2") (pintype "passive"))
    )
    (net (code "49") (name "Net-(IC2A-OUT)") (class "Default")
      (node (ref "C17") (pin "2") (pinfunction "2_2") (pintype "passive"))
      (node (ref "IC2") (pin "1") (pinfunction "OUT_1") (pintype "output"))
      (node (ref "Q2") (pin "B") (pinfunction "B_B") (pintype "passive"))
      (node (ref "R20") (pin "2") (pinfunction "2_2") (pintype "passive"))
    )
    (net (code "50") (name "Net-(IC2B--IN)") (class "Default")
      (node (ref "C7") (pin "2") (pinfunction "2_2") (pintype "passive"))
      (node (ref "IC2") (pin "6") (pinfunction "-IN_6") (pintype "input"))
      (node (ref "Q3") (pin "C") (pinfunction "C_C") (pintype "passive"))
      (node (ref "R19") (pin "2") (pinfunction "2_2") (pintype "passive"))
    )
    (net (code "51") (name "Net-(IC2B-OUT)") (class "Default")
      (node (ref "C7") (pin "1") (pinfunction "1_1") (pintype "passive"))
      (node (ref "IC2") (pin "7") (pinfunction "OUT_7") (pintype "output"))
      (node (ref "R8") (pin "1") (pinfunction "1_1") (pintype "passive"))
    )
    (net (code "52") (name "Net-(IC3B-B)") (class "Default")
      (node (ref "C2") (pin "2") (pinfunction "2_2") (pintype "passive"))
      (node (ref "IC3") (pin "10") (pinfunction "B_10") (pintype "passive"))
      (node (ref "IC3") (pin "12") (pinfunction "OUT_12") (pintype "output"))
    )
    (net (code "53") (name "Net-(IC3C-IN_N)") (class "Default")
      (node (ref "IC3") (pin "4") (pinfunction "IN_N_4") (pintype "input"))
      (node (ref "IC6") (pin "5") (pinfunction "OUT_5") (pintype "output"))
      (node (ref "R23") (pin "2") (pinfunction "2_2") (pintype "passive"))
      (node (ref "R24") (pin "2") (pinfunction "2_2") (pintype "passive"))
      (node (ref "R25") (pin "1") (pinfunction "1_1") (pintype "passive"))
    )
    (net (code "54") (name "Net-(IC3D-IN_N)") (class "Default")
      (node (ref "IC3") (pin "13") (pinfunction "IN_N_13") (pintype "input"))
      (node (ref "R1") (pin "2") (pinfunction "2_2") (pintype "passive"))
      (node (ref "R2") (pin "2") (pinfunction "2_2") (pintype "passive"))
      (node (ref "R3") (pin "1") (pinfunction "1_1") (pintype "passive"))
    )
    (net (code "55") (name "Net-(IC4A-B)") (class "Default")
      (node (ref "C20") (pin "2") (pinfunction "2_2") (pintype "passive"))
      (node (ref "IC4") (pin "5") (pinfunction "OUT_5") (pintype "output"))
      (node (ref "IC4") (pin "7") (pinfunction "B_7") (pintype "passive"))
    )
    (net (code "56") (name "Net-(IC4B-B)") (class "Default")
      (node (ref "C8") (pin "2") (pinfunction "2_2") (pintype "passive"))
      (node (ref "IC4") (pin "10") (pinfunction "B_10") (pintype "passive"))
      (node (ref "IC4") (pin "12") (pinfunction "OUT_12") (pintype "output"))
    )
    (net (code "57") (name "Net-(IC4C-IN_N)") (class "Default")
      (node (ref "IC4") (pin "4") (pinfunction "IN_N_4") (pintype "input"))
      (node (ref "R27") (pin "2") (pinfunction "2_2") (pintype "passive"))
      (node (ref "R28") (pin "2") (pinfunction "2_2") (pintype "passive"))
      (node (ref "R29") (pin "1") (pinfunction "1_1") (pintype "passive"))
    )
    (net (code "58") (name "Net-(IC4D-IN_N)") (class "Default")
      (node (ref "IC4") (pin "13") (pinfunction "IN_N_13") (pintype "input"))
      (node (ref "R10") (pin "2") (pinfunction "2_2") (pintype "passive"))
      (node (ref "R11") (pin "1") (pinfunction "1_1") (pintype "passive"))
      (node (ref "R9") (pin "2") (pinfunction "2_2") (pintype "passive"))
    )
    (net (code "59") (name "Net-(IC5A--IN)") (class "Default")
      (node (ref "C22") (pin "2") (pinfunction "2_2") (pintype "passive"))
      (node (ref "IC5") (pin "2") (pinfunction "-IN_2") (pintype "input"))
      (node (ref "IC7") (pin "13") (pinfunction "X_13") (pintype "bidirectional"))
      (node (ref "R31") (pin "2") (pinfunction "2_2") (pintype "passive"))
    )
    (net (code "60") (name "Net-(IC5B--IN)") (class "Default")
      (node (ref "C11") (pin "1") (pinfunction "1_1") (pintype "passive"))
      (node (ref "IC5") (pin "6") (pinfunction "-IN_6") (pintype "input"))
      (node (ref "IC6") (pin "12") (pinfunction "OUT_12") (pintype "output"))
      (node (ref "R13") (pin "2") (pinfunction "2_2") (pintype "passive"))
    )
    (net (code "61") (name "Net-(IC6C-IN_N)") (class "Default")
      (node (ref "IC6") (pin "4") (pinfunction "IN_N_4") (pintype "input"))
      (node (ref "R34") (pin "1") (pinfunction "1_1") (pintype "passive"))
      (node (ref "R35") (pin "1") (pinfunction "1_1") (pintype "passive"))
    )
    (net (code "62") (name "Net-(IC6C-IN_P)") (class "Default")
      (node (ref "IC6") (pin "3") (pinfunction "IN_P_3") (pintype "input"))
      (node (ref "R32") (pin "1") (pinfunction "1_1") (pintype "passive"))
      (node (ref "R33") (pin "2") (pinfunction "2_2") (pintype "passive"))
    )
    (net (code "63") (name "Net-(IC6D-IN_P)") (class "Default")
      (node (ref "IC6") (pin "14") (pinfunction "IN_P_14") (pintype "input"))
      (node (ref "R14") (pin "1") (pinfunction "1_1") (pintype "passive"))
      (node (ref "R15") (pin "2") (pinfunction "2_2") (pintype "passive"))
    )
    (net (code "64") (name "Net-(IC7A-Y0)") (class "Default")
      (node (ref "C28") (pin "1") (pinfunction "1_1") (pintype "passive"))
      (node (ref "IC7") (pin "1") (pinfunction "Y0_1") (pintype "bidirectional"))
      (node (ref "IC7") (pin "5") (pinfunction "Y1_5") (pintype "bidirectional"))
    )
    (net (code "65") (name "Net-(IC7A-Y2)") (class "Default")
      (node (ref "C30") (pin "1") (pinfunction "1_1") (pintype "passive"))
      (node (ref "IC7") (pin "2") (pinfunction "Y2_2") (pintype "bidirectional"))
      (node (ref "IC7") (pin "4") (pinfunction "Y3_4") (pintype "bidirectional"))
    )
    (net (code "66") (name "Net-(JP4-Pad2)") (class "Default")
      (node (ref "JP4") (pin "2") (pinfunction "2_2") (pintype "passive"))
      (node (ref "R53") (pin "1") (pinfunction "1_1") (pintype "passive"))
    )
    (net (code "67") (name "Net-(JP4-Pad3)") (class "Default")
      (node (ref "JP4") (pin "3") (pinfunction "3_3") (pintype "passive"))
      (node (ref "R52") (pin "1") (pinfunction "1_1") (pintype "passive"))
    )
    (net (code "68") (name "Net-(JP4-Pad4)") (class "Default")
      (node (ref "JP4") (pin "4") (pinfunction "4_4") (pintype "passive"))
      (node (ref "R42") (pin "1") (pinfunction "1_1") (pintype "passive"))
    )
    (net (code "69") (name "Net-(LED1-PadA)") (class "Default")
      (node (ref "LED1") (pin "A") (pinfunction "A_A") (pintype "passive"))
      (node (ref "R51") (pin "1") (pinfunction "1_1") (pintype "passive"))
    )
    (net (code "70") (name "Net-(LED2-PadA)") (class "Default")
      (node (ref "LED2") (pin "A") (pinfunction "A_A") (pintype "passive"))
      (node (ref "R54") (pin "1") (pinfunction "1_1") (pintype "passive"))
    )
    (net (code "71") (name "Net-(Q1-PadE)") (class "Default")
      (node (ref "Q1") (pin "E") (pinfunction "E_E") (pintype "passive"))
      (node (ref "R6") (pin "2") (pinfunction "2_2") (pintype "passive"))
    )
    (net (code "72") (name "Net-(Q2-PadE)") (class "Default")
      (node (ref "Q2") (pin "E") (pinfunction "E_E") (pintype "passive"))
      (node (ref "Q3") (pin "E") (pinfunction "E_E") (pintype "passive"))
      (node (ref "R8") (pin "2") (pinfunction "2_2") (pintype "passive"))
    )
    (net (code "73") (name "Net-(Q4-PadE)") (class "Default")
      (node (ref "Q4") (pin "E") (pinfunction "E_E") (pintype "passive"))
      (node (ref "R17") (pin "2") (pinfunction "2_2") (pintype "passive"))
    )
    (net (code "74") (name "Net-(R5-Pad2)") (class "Default")
      (node (ref "R5") (pin "2") (pinfunction "2_2") (pintype "passive"))
      (node (ref "SJ1") (pin "2") (pinfunction "2_2") (pintype "passive"))
    )
    (net (code "75") (name "Net-(R16-A)") (class "Default")
      (node (ref "R16") (pin "1") (pinfunction "A_1") (pintype "passive"))
      (node (ref "R16") (pin "2") (pinfunction "S_2") (pintype "passive"))
      (node (ref "R21") (pin "1") (pinfunction "1_1") (pintype "passive"))
      (node (ref "SJ1") (pin "1") (pinfunction "1_1") (pintype "passive"))
    )
    (net (code "76") (name "Net-(R37-A)") (class "Default")
      (node (ref "R22") (pin "1") (pinfunction "1_1") (pintype "passive"))
      (node (ref "R37") (pin "1") (pinfunction "A_1") (pintype "passive"))
      (node (ref "R37") (pin "2") (pinfunction "S_2") (pintype "passive"))
    )
    (net (code "77") (name "Net-(U1-(ADC4{slash}SDA{slash}PCINT12)PC4)") (class "Default")
      (node (ref "R54") (pin "2") (pinfunction "2_2") (pintype "passive"))
      (node (ref "U1") (pin "27") (pinfunction "(ADC4/SDA/PCINT12)PC4_27") (pintype "bidirectional"))
    )
    (net (code "78") (name "Net-(U1-(ADC5{slash}SCL{slash}PCINT13)PC5)") (class "Default")
      (node (ref "R51") (pin "2") (pinfunction "2_2") (pintype "passive"))
      (node (ref "U1") (pin "28") (pinfunction "(ADC5/SCL/PCINT13)PC5_28") (pintype "bidirectional"))
    )
    (net (code "79") (name "Net-(U1-(PCINT6{slash}XTAL1{slash}TOSC1)PB6)") (class "Default")
      (node (ref "C36") (pin "2") (pinfunction "2_2") (pintype "passive"))
      (node (ref "Q5") (pin "1") (pinfunction "1_1") (pintype "passive"))
      (node (ref "U1") (pin "7") (pinfunction "(PCINT6/XTAL1/TOSC1)PB6_7") (pintype "bidirectional"))
    )
    (net (code "80") (name "Net-(U1-(PCINT7{slash}XTAL2{slash}TOSC2)PB7)") (class "Default")
      (node (ref "C37") (pin "2") (pinfunction "2_2") (pintype "passive"))
      (node (ref "Q5") (pin "2") (pinfunction "2_2") (pintype "passive"))
      (node (ref "U1") (pin "8") (pinfunction "(PCINT7/XTAL2/TOSC2)PB7_8") (pintype "bidirectional"))
    )
    (net (code "81") (name "VCC") (class "Default")
      (node (ref "C1") (pin "+") (pinfunction "+_+") (pintype "passive"))
      (node (ref "C10") (pin "1") (pinfunction "1_1") (pintype "passive"))
      (node (ref "C13") (pin "1") (pinfunction "1_1") (pintype "passive"))
      (node (ref "C29") (pin "1") (pinfunction "1_1") (pintype "passive"))
      (node (ref "C3") (pin "1") (pinfunction "1_1") (pintype "passive"))
      (node (ref "C4") (pin "1") (pinfunction "1_1") (pintype "passive"))
      (node (ref "C6") (pin "1") (pinfunction "1_1") (pintype "passive"))
      (node (ref "C9") (pin "1") (pinfunction "1_1") (pintype "passive"))
      (node (ref "IC1") (pin "8") (pinfunction "V+_8") (pintype "power_in"))
      (node (ref "IC2") (pin "8") (pinfunction "V+_8") (pintype "power_in"))
      (node (ref "IC3") (pin "11") (pinfunction "V+_11") (pintype "power_in"))
      (node (ref "IC4") (pin "11") (pinfunction "V+_11") (pintype "power_in"))
      (node (ref "IC5") (pin "8") (pinfunction "V+_8") (pintype "power_in"))
      (node (ref "IC6") (pin "11") (pinfunction "V+_11") (pintype "power_in"))
      (node (ref "IC7") (pin "16") (pinfunction "VCC_16") (pintype "power_in"))
      (node (ref "JP2") (pin "4") (pinfunction "4_4") (pintype "passive"))
      (node (ref "R62") (pin "1") (pinfunction "1_1") (pintype "passive"))
      (node (ref "R63") (pin "1") (pinfunction "1_1") (pintype "passive"))
    )
    (net (code "82") (name "VEE") (class "Default")
      (node (ref "C14") (pin "-") (pinfunction "-_-") (pintype "passive"))
      (node (ref "C16") (pin "2") (pinfunction "2_2") (pintype "passive"))
      (node (ref "C18") (pin "2") (pinfunction "2_2") (pintype "passive"))
      (node (ref "C19") (pin "2") (pinfunction "2_2") (pintype "passive"))
      (node (ref "C21") (pin "2") (pinfunction "2_2") (pintype "passive"))
      (node (ref "C23") (pin "2") (pinfunction "2_2") (pintype "passive"))
      (node (ref "C25") (pin "2") (pinfunction "2_2") (pintype "passive"))
      (node (ref "C34") (pin "2") (pinfunction "2_2") (pintype "passive"))
      (node (ref "IC1") (pin "4") (pinfunction "V-_4") (pintype "power_in"))
      (node (ref "IC2") (pin "4") (pinfunction "V-_4") (pintype "power_in"))
      (node (ref "IC3") (pin "6") (pinfunction "V-_6") (pintype "power_in"))
      (node (ref "IC4") (pin "6") (pinfunction "V-_6") (pintype "power_in"))
      (node (ref "IC5") (pin "4") (pinfunction "V-_4") (pintype "power_in"))
      (node (ref "IC6") (pin "6") (pinfunction "V-_6") (pintype "power_in"))
      (node (ref "IC7") (pin "7") (pinfunction "VEE_7") (pintype "power_in"))
      (node (ref "JP2") (pin "2") (pinfunction "2_2") (pintype "passive"))
      (node (ref "R12") (pin "1") (pinfunction "1_1") (pintype "passive"))
      (node (ref "R26") (pin "1") (pinfunction "1_1") (pintype "passive"))
      (node (ref "R30") (pin "1") (pinfunction "1_1") (pintype "passive"))
      (node (ref "R36") (pin "2") (pinfunction "2_2") (pintype "passive"))
      (node (ref "R4") (pin "1") (pinfunction "1_1") (pintype "passive"))
    )
    (net (code "83") (name "unconnected-(IC3C-I_DIODE-Pad2)") (class "Default")
      (node (ref "IC3") (pin "2") (pinfunction "I_DIODE_2") (pintype "input"))
    )
    (net (code "84") (name "unconnected-(IC3D-I_DIODE-Pad15)") (class "Default")
      (node (ref "IC3") (pin "15") (pinfunction "I_DIODE_15") (pintype "input"))
    )
    (net (code "85") (name "unconnected-(IC4C-I_DIODE-Pad2)") (class "Default")
      (node (ref "IC4") (pin "2") (pinfunction "I_DIODE_2") (pintype "input"))
    )
    (net (code "86") (name "unconnected-(IC4D-I_DIODE-Pad15)") (class "Default")
      (node (ref "IC4") (pin "15") (pinfunction "I_DIODE_15") (pintype "input"))
    )
    (net (code "87") (name "unconnected-(IC6A-B-Pad7)") (class "Default")
      (node (ref "IC6") (pin "7") (pinfunction "B_7") (pintype "passive"))
    )
    (net (code "88") (name "unconnected-(IC6A-E-Pad8)") (class "Default")
      (node (ref "IC6") (pin "8") (pinfunction "E_8") (pintype "passive"))
    )
    (net (code "89") (name "unconnected-(IC6B-B-Pad10)") (class "Default")
      (node (ref "IC6") (pin "10") (pinfunction "B_10") (pintype "passive"))
    )
    (net (code "90") (name "unconnected-(IC6B-E-Pad9)") (class "Default")
      (node (ref "IC6") (pin "9") (pinfunction "E_9") (pintype "passive"))
    )
    (net (code "91") (name "unconnected-(IC6C-I_DIODE-Pad2)") (class "Default")
      (node (ref "IC6") (pin "2") (pinfunction "I_DIODE_2") (pintype "input"))
    )
    (net (code "92") (name "unconnected-(IC6D-I_DIODE-Pad15)") (class "Default")
      (node (ref "IC6") (pin "15") (pinfunction "I_DIODE_15") (pintype "input"))
    )
    (net (code "93") (name "unconnected-(U1-(ADC2{slash}PCINT10)PC2-Pad25)") (class "Default")
      (node (ref "U1") (pin "25") (pinfunction "(ADC2/PCINT10)PC2_25") (pintype "bidirectional"))
    )
    (net (code "94") (name "unconnected-(U1-(ADC3{slash}PCINT11)PC3-Pad26)") (class "Default")
      (node (ref "U1") (pin "26") (pinfunction "(ADC3/PCINT11)PC3_26") (pintype "bidirectional"))
    )
    (net (code "95") (name "unconnected-(U1-ADC6-Pad19)") (class "Default")
      (node (ref "U1") (pin "19") (pinfunction "ADC6_19") (pintype "input"))
    )
    (net (code "96") (name "unconnected-(U1-ADC7-Pad22)") (class "Default")
      (node (ref "U1") (pin "22") (pinfunction "ADC7_22") (pintype "input"))
    )
    (net (code "97") (name "unconnected-(U1-PD0(RXD{slash}PCINT16)-Pad30)") (class "Default")
      (node (ref "U1") (pin "30") (pinfunction "PD0(RXD/PCINT16)_30") (pintype "bidirectional"))
    )
    (net (code "98") (name "unconnected-(U1-PD3(PCINT19{slash}OC2B{slash}INT1)-Pad1)") (class "Default")
      (node (ref "U1") (pin "1") (pinfunction "PD3(PCINT19/OC2B/INT1)_1") (pintype "bidirectional"))
    )
    (net (code "99") (name "unconnected-(U1-PD7(PCINT23{slash}AIN1)-Pad11)") (class "Default")
      (node (ref "U1") (pin "11") (pinfunction "PD7(PCINT23/AIN1)_11") (pintype "bidirectional"))
    )
  )
)
